# AMC.net
KiCad netlist of a schematic drawn in Altium Designer
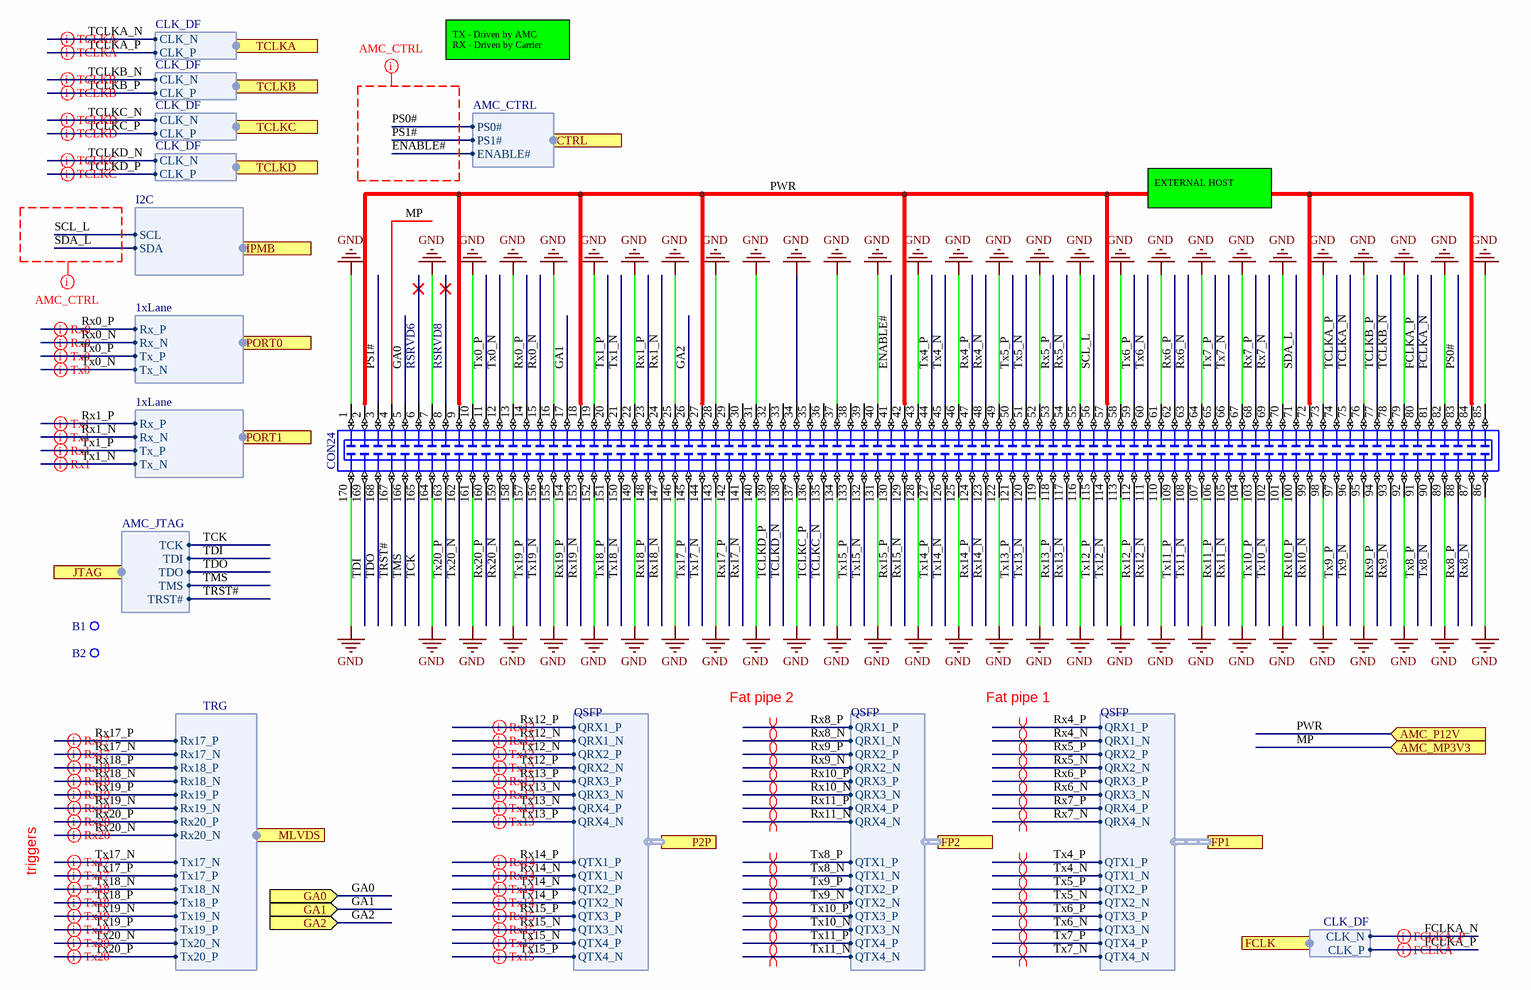
[diagram p0: AMC.SchDoc]

(export (version "E")
  (design (tool "Eeschema 10.0.6"))
  (components
    (comp (ref "B1")
      (value "Plated Hole")
      (footprint "MTG320_550")
      (description "Single Terminal Socket")
      (fields (field (name "PART NUMBER") "PLATED_HOLE3.2_PAD5.5") (field (name "AUTHOR") "CERN DEM JMW"))
      (libsource (lib "Eletro-mechanical") (part "Single Terminal Socket"))
    )
    (comp (ref "B2")
      (value "Plated Hole")
      (footprint "MTG320_550")
      (description "Single Terminal Socket")
      (fields (field (name "PART NUMBER") "PLATED_HOLE3.2_PAD5.5") (field (name "AUTHOR") "CERN DEM JMW"))
      (libsource (lib "Eletro-mechanical") (part "Single Terminal Socket"))
    )
    (comp (ref "CON24")
      (value "SAMTEC_MTCA-085-02-S-DV-SMT-K-TR")
      (footprint "SAMTEC_MTCA-085-02-S-DV-SMT-K-TR")
      (description "170 Poles,  Micro TCA (Telecom Computing Architecture) Edge Card Socket")
      (fields
        (field (name "MANUFACTURER") "SAMTEC")
        (field (name "MANUFACTURER PART NUMBER") "MTCA-085-02-S-DV-SMT-K-TR")
        (field (name "AUTHOR") "CERN DEM JLC")
      )
      (libsource (lib "Connectors") (part "Micro TCA Female 170"))
    )
  )
  (nets
    (net (code "8") (name "/ENABLE#") (class "Default")
      (node (ref "CON24") (pin "41") (pinfunction "41_41") (pintype "bidirectional"))
    )
    (net (code "9") (name "/FCLKA_N") (class "Default")
      (node (ref "CON24") (pin "81") (pinfunction "81_81") (pintype "bidirectional"))
    )
    (net (code "10") (name "/FCLKA_P") (class "Default")
      (node (ref "CON24") (pin "80") (pinfunction "80_80") (pintype "bidirectional"))
    )
    (net (code "11") (name "/GA0") (class "Default")
      (node (ref "CON24") (pin "5") (pinfunction "5_5") (pintype "bidirectional"))
    )
    (net (code "12") (name "/GA1") (class "Default")
      (node (ref "CON24") (pin "17") (pinfunction "17_17") (pintype "bidirectional"))
    )
    (net (code "13") (name "/GA2") (class "Default")
      (node (ref "CON24") (pin "26") (pinfunction "26_26") (pintype "bidirectional"))
    )
    (net (code "14") (name "/MP") (class "Default")
      (node (ref "CON24") (pin "4") (pinfunction "4_4") (pintype "bidirectional"))
    )
    (net (code "15") (name "/PS0#") (class "Default")
      (node (ref "CON24") (pin "83") (pinfunction "83_83") (pintype "bidirectional"))
    )
    (net (code "16") (name "/PS1#") (class "Default")
      (node (ref "CON24") (pin "3") (pinfunction "3_3") (pintype "bidirectional"))
    )
    (net (code "17") (name "/PWR") (class "Default")
      (node (ref "CON24") (pin "18") (pinfunction "18_18") (pintype "bidirectional"))
      (node (ref "CON24") (pin "2") (pinfunction "2_2") (pintype "bidirectional"))
      (node (ref "CON24") (pin "27") (pinfunction "27_27") (pintype "bidirectional"))
      (node (ref "CON24") (pin "42") (pinfunction "42_42") (pintype "bidirectional"))
      (node (ref "CON24") (pin "57") (pinfunction "57_57") (pintype "bidirectional"))
      (node (ref "CON24") (pin "72") (pinfunction "72_72") (pintype "bidirectional"))
      (node (ref "CON24") (pin "84") (pinfunction "84_84") (pintype "bidirectional"))
      (node (ref "CON24") (pin "9") (pinfunction "9_9") (pintype "bidirectional"))
    )
    (net (code "18") (name "/Rx0_N") (class "Default")
      (node (ref "CON24") (pin "15") (pinfunction "15_15") (pintype "bidirectional"))
    )
    (net (code "19") (name "/Rx0_P") (class "Default")
      (node (ref "CON24") (pin "14") (pinfunction "14_14") (pintype "bidirectional"))
    )
    (net (code "20") (name "/Rx1_N") (class "Default")
      (node (ref "CON24") (pin "24") (pinfunction "24_24") (pintype "bidirectional"))
    )
    (net (code "21") (name "/Rx1_P") (class "Default")
      (node (ref "CON24") (pin "23") (pinfunction "23_23") (pintype "bidirectional"))
    )
    (net (code "22") (name "/Rx4_N") (class "Default")
      (node (ref "CON24") (pin "48") (pinfunction "48_48") (pintype "bidirectional"))
    )
    (net (code "23") (name "/Rx4_P") (class "Default")
      (node (ref "CON24") (pin "47") (pinfunction "47_47") (pintype "bidirectional"))
    )
    (net (code "24") (name "/Rx5_N") (class "Default")
      (node (ref "CON24") (pin "54") (pinfunction "54_54") (pintype "bidirectional"))
    )
    (net (code "25") (name "/Rx5_P") (class "Default")
      (node (ref "CON24") (pin "53") (pinfunction "53_53") (pintype "bidirectional"))
    )
    (net (code "26") (name "/Rx6_N") (class "Default")
      (node (ref "CON24") (pin "63") (pinfunction "63_63") (pintype "bidirectional"))
    )
    (net (code "27") (name "/Rx6_P") (class "Default")
      (node (ref "CON24") (pin "62") (pinfunction "62_62") (pintype "bidirectional"))
    )
    (net (code "28") (name "/Rx7_N") (class "Default")
      (node (ref "CON24") (pin "69") (pinfunction "69_69") (pintype "bidirectional"))
    )
    (net (code "29") (name "/Rx7_P") (class "Default")
      (node (ref "CON24") (pin "68") (pinfunction "68_68") (pintype "bidirectional"))
    )
    (net (code "30") (name "/Rx8_N") (class "Default")
      (node (ref "CON24") (pin "87") (pinfunction "87_87") (pintype "bidirectional"))
    )
    (net (code "31") (name "/Rx8_P") (class "Default")
      (node (ref "CON24") (pin "88") (pinfunction "88_88") (pintype "bidirectional"))
    )
    (net (code "32") (name "/Rx9_N") (class "Default")
      (node (ref "CON24") (pin "93") (pinfunction "93_93") (pintype "bidirectional"))
    )
    (net (code "33") (name "/Rx9_P") (class "Default")
      (node (ref "CON24") (pin "94") (pinfunction "94_94") (pintype "bidirectional"))
    )
    (net (code "34") (name "/Rx10_N") (class "Default")
      (node (ref "CON24") (pin "99") (pinfunction "99_99") (pintype "bidirectional"))
    )
    (net (code "35") (name "/Rx10_P") (class "Default")
      (node (ref "CON24") (pin "100") (pinfunction "100_100") (pintype "bidirectional"))
    )
    (net (code "36") (name "/Rx11_N") (class "Default")
      (node (ref "CON24") (pin "105") (pinfunction "105_105") (pintype "bidirectional"))
    )
    (net (code "37") (name "/Rx11_P") (class "Default")
      (node (ref "CON24") (pin "106") (pinfunction "106_106") (pintype "bidirectional"))
    )
    (net (code "38") (name "/Rx12_N") (class "Default")
      (node (ref "CON24") (pin "111") (pinfunction "111_111") (pintype "bidirectional"))
    )
    (net (code "39") (name "/Rx12_P") (class "Default")
      (node (ref "CON24") (pin "112") (pinfunction "112_112") (pintype "bidirectional"))
    )
    (net (code "40") (name "/Rx13_N") (class "Default")
      (node (ref "CON24") (pin "117") (pinfunction "117_117") (pintype "bidirectional"))
    )
    (net (code "41") (name "/Rx13_P") (class "Default")
      (node (ref "CON24") (pin "118") (pinfunction "118_118") (pintype "bidirectional"))
    )
    (net (code "42") (name "/Rx14_N") (class "Default")
      (node (ref "CON24") (pin "123") (pinfunction "123_123") (pintype "bidirectional"))
    )
    (net (code "43") (name "/Rx14_P") (class "Default")
      (node (ref "CON24") (pin "124") (pinfunction "124_124") (pintype "bidirectional"))
    )
    (net (code "44") (name "/Rx15_N") (class "Default")
      (node (ref "CON24") (pin "129") (pinfunction "129_129") (pintype "bidirectional"))
    )
    (net (code "45") (name "/Rx15_P") (class "Default")
      (node (ref "CON24") (pin "130") (pinfunction "130_130") (pintype "bidirectional"))
    )
    (net (code "46") (name "/Rx17_N") (class "Default")
      (node (ref "CON24") (pin "141") (pinfunction "141_141") (pintype "bidirectional"))
    )
    (net (code "47") (name "/Rx17_P") (class "Default")
      (node (ref "CON24") (pin "142") (pinfunction "142_142") (pintype "bidirectional"))
    )
    (net (code "48") (name "/Rx18_N") (class "Default")
      (node (ref "CON24") (pin "147") (pinfunction "147_147") (pintype "bidirectional"))
    )
    (net (code "49") (name "/Rx18_P") (class "Default")
      (node (ref "CON24") (pin "148") (pinfunction "148_148") (pintype "bidirectional"))
    )
    (net (code "50") (name "/Rx19_N") (class "Default")
      (node (ref "CON24") (pin "153") (pinfunction "153_153") (pintype "bidirectional"))
    )
    (net (code "51") (name "/Rx19_P") (class "Default")
      (node (ref "CON24") (pin "154") (pinfunction "154_154") (pintype "bidirectional"))
    )
    (net (code "52") (name "/Rx20_N") (class "Default")
      (node (ref "CON24") (pin "159") (pinfunction "159_159") (pintype "bidirectional"))
    )
    (net (code "53") (name "/Rx20_P") (class "Default")
      (node (ref "CON24") (pin "160") (pinfunction "160_160") (pintype "bidirectional"))
    )
    (net (code "54") (name "/SCL_L") (class "Default")
      (node (ref "CON24") (pin "56") (pinfunction "56_56") (pintype "bidirectional"))
    )
    (net (code "55") (name "/SDA_L") (class "Default")
      (node (ref "CON24") (pin "71") (pinfunction "71_71") (pintype "bidirectional"))
    )
    (net (code "56") (name "/TCK") (class "Default")
      (node (ref "CON24") (pin "165") (pinfunction "165_165") (pintype "bidirectional"))
    )
    (net (code "57") (name "/TCLKA_N") (class "Default")
      (node (ref "CON24") (pin "75") (pinfunction "75_75") (pintype "bidirectional"))
    )
    (net (code "58") (name "/TCLKA_P") (class "Default")
      (node (ref "CON24") (pin "74") (pinfunction "74_74") (pintype "bidirectional"))
    )
    (net (code "59") (name "/TCLKB_N") (class "Default")
      (node (ref "CON24") (pin "78") (pinfunction "78_78") (pintype "bidirectional"))
    )
    (net (code "60") (name "/TCLKB_P") (class "Default")
      (node (ref "CON24") (pin "77") (pinfunction "77_77") (pintype "bidirectional"))
    )
    (net (code "61") (name "/TCLKC_N") (class "Default")
      (node (ref "CON24") (pin "135") (pinfunction "135_135") (pintype "bidirectional"))
    )
    (net (code "62") (name "/TCLKC_P") (class "Default")
      (node (ref "CON24") (pin "136") (pinfunction "136_136") (pintype "bidirectional"))
    )
    (net (code "63") (name "/TCLKD_N") (class "Default")
      (node (ref "CON24") (pin "138") (pinfunction "138_138") (pintype "bidirectional"))
    )
    (net (code "64") (name "/TCLKD_P") (class "Default")
      (node (ref "CON24") (pin "139") (pinfunction "139_139") (pintype "bidirectional"))
    )
    (net (code "65") (name "/TDI") (class "Default")
      (node (ref "CON24") (pin "169") (pinfunction "169_169") (pintype "bidirectional"))
    )
    (net (code "66") (name "/TDO") (class "Default")
      (node (ref "CON24") (pin "168") (pinfunction "168_168") (pintype "bidirectional"))
    )
    (net (code "67") (name "/TMS") (class "Default")
      (node (ref "CON24") (pin "166") (pinfunction "166_166") (pintype "bidirectional"))
    )
    (net (code "68") (name "/TRST#") (class "Default")
      (node (ref "CON24") (pin "167") (pinfunction "167_167") (pintype "bidirectional"))
    )
    (net (code "69") (name "/Tx0_N") (class "Default")
      (node (ref "CON24") (pin "12") (pinfunction "12_12") (pintype "bidirectional"))
    )
    (net (code "70") (name "/Tx0_P") (class "Default")
      (node (ref "CON24") (pin "11") (pinfunction "11_11") (pintype "bidirectional"))
    )
    (net (code "71") (name "/Tx1_N") (class "Default")
      (node (ref "CON24") (pin "21") (pinfunction "21_21") (pintype "bidirectional"))
    )
    (net (code "72") (name "/Tx1_P") (class "Default")
      (node (ref "CON24") (pin "20") (pinfunction "20_20") (pintype "bidirectional"))
    )
    (net (code "73") (name "/Tx4_N") (class "Default")
      (node (ref "CON24") (pin "45") (pinfunction "45_45") (pintype "bidirectional"))
    )
    (net (code "74") (name "/Tx4_P") (class "Default")
      (node (ref "CON24") (pin "44") (pinfunction "44_44") (pintype "bidirectional"))
    )
    (net (code "75") (name "/Tx5_N") (class "Default")
      (node (ref "CON24") (pin "51") (pinfunction "51_51") (pintype "bidirectional"))
    )
    (net (code "76") (name "/Tx5_P") (class "Default")
      (node (ref "CON24") (pin "50") (pinfunction "50_50") (pintype "bidirectional"))
    )
    (net (code "77") (name "/Tx6_N") (class "Default")
      (node (ref "CON24") (pin "60") (pinfunction "60_60") (pintype "bidirectional"))
    )
    (net (code "78") (name "/Tx6_P") (class "Default")
      (node (ref "CON24") (pin "59") (pinfunction "59_59") (pintype "bidirectional"))
    )
    (net (code "79") (name "/Tx7_N") (class "Default")
      (node (ref "CON24") (pin "66") (pinfunction "66_66") (pintype "bidirectional"))
    )
    (net (code "80") (name "/Tx7_P") (class "Default")
      (node (ref "CON24") (pin "65") (pinfunction "65_65") (pintype "bidirectional"))
    )
    (net (code "81") (name "/Tx8_N") (class "Default")
      (node (ref "CON24") (pin "90") (pinfunction "90_90") (pintype "bidirectional"))
    )
    (net (code "82") (name "/Tx8_P") (class "Default")
      (node (ref "CON24") (pin "91") (pinfunction "91_91") (pintype "bidirectional"))
    )
    (net (code "83") (name "/Tx9_N") (class "Default")
      (node (ref "CON24") (pin "96") (pinfunction "96_96") (pintype "bidirectional"))
    )
    (net (code "84") (name "/Tx9_P") (class "Default")
      (node (ref "CON24") (pin "97") (pinfunction "97_97") (pintype "bidirectional"))
    )
    (net (code "85") (name "/Tx10_N") (class "Default")
      (node (ref "CON24") (pin "102") (pinfunction "102_102") (pintype "bidirectional"))
    )
    (net (code "86") (name "/Tx10_P") (class "Default")
      (node (ref "CON24") (pin "103") (pinfunction "103_103") (pintype "bidirectional"))
    )
    (net (code "87") (name "/Tx11_N") (class "Default")
      (node (ref "CON24") (pin "108") (pinfunction "108_108") (pintype "bidirectional"))
    )
    (net (code "88") (name "/Tx11_P") (class "Default")
      (node (ref "CON24") (pin "109") (pinfunction "109_109") (pintype "bidirectional"))
    )
    (net (code "89") (name "/Tx12_N") (class "Default")
      (node (ref "CON24") (pin "114") (pinfunction "114_114") (pintype "bidirectional"))
    )
    (net (code "90") (name "/Tx12_P") (class "Default")
      (node (ref "CON24") (pin "115") (pinfunction "115_115") (pintype "bidirectional"))
    )
    (net (code "91") (name "/Tx13_N") (class "Default")
      (node (ref "CON24") (pin "120") (pinfunction "120_120") (pintype "bidirectional"))
    )
    (net (code "92") (name "/Tx13_P") (class "Default")
      (node (ref "CON24") (pin "121") (pinfunction "121_121") (pintype "bidirectional"))
    )
    (net (code "93") (name "/Tx14_N") (class "Default")
      (node (ref "CON24") (pin "126") (pinfunction "126_126") (pintype "bidirectional"))
    )
    (net (code "94") (name "/Tx14_P") (class "Default")
      (node (ref "CON24") (pin "127") (pinfunction "127_127") (pintype "bidirectional"))
    )
    (net (code "95") (name "/Tx15_N") (class "Default")
      (node (ref "CON24") (pin "132") (pinfunction "132_132") (pintype "bidirectional"))
    )
    (net (code "96") (name "/Tx15_P") (class "Default")
      (node (ref "CON24") (pin "133") (pinfunction "133_133") (pintype "bidirectional"))
    )
    (net (code "97") (name "/Tx17_N") (class "Default")
      (node (ref "CON24") (pin "144") (pinfunction "144_144") (pintype "bidirectional"))
    )
    (net (code "98") (name "/Tx17_P") (class "Default")
      (node (ref "CON24") (pin "145") (pinfunction "145_145") (pintype "bidirectional"))
    )
    (net (code "99") (name "/Tx18_N") (class "Default")
      (node (ref "CON24") (pin "150") (pinfunction "150_150") (pintype "bidirectional"))
    )
    (net (code "100") (name "/Tx18_P") (class "Default")
      (node (ref "CON24") (pin "151") (pinfunction "151_151") (pintype "bidirectional"))
    )
    (net (code "101") (name "/Tx19_N") (class "Default")
      (node (ref "CON24") (pin "156") (pinfunction "156_156") (pintype "bidirectional"))
    )
    (net (code "102") (name "/Tx19_P") (class "Default")
      (node (ref "CON24") (pin "157") (pinfunction "157_157") (pintype "bidirectional"))
    )
    (net (code "103") (name "/Tx20_N") (class "Default")
      (node (ref "CON24") (pin "162") (pinfunction "162_162") (pintype "bidirectional"))
    )
    (net (code "104") (name "/Tx20_P") (class "Default")
      (node (ref "CON24") (pin "163") (pinfunction "163_163") (pintype "bidirectional"))
    )
    (net (code "112") (name "GND") (class "Default")
      (node (ref "CON24") (pin "1") (pinfunction "1_1") (pintype "bidirectional"))
      (node (ref "CON24") (pin "10") (pinfunction "10_10") (pintype "bidirectional"))
      (node (ref "CON24") (pin "101") (pinfunction "101_101") (pintype "bidirectional"))
      (node (ref "CON24") (pin "104") (pinfunction "104_104") (pintype "bidirectional"))
      (node (ref "CON24") (pin "107") (pinfunction "107_107") (pintype "bidirectional"))
      (node (ref "CON24") (pin "110") (pinfunction "110_110") (pintype "bidirectional"))
      (node (ref "CON24") (pin "113") (pinfunction "113_113") (pintype "bidirectional"))
      (node (ref "CON24") (pin "116") (pinfunction "116_116") (pintype "bidirectional"))
      (node (ref "CON24") (pin "119") (pinfunction "119_119") (pintype "bidirectional"))
      (node (ref "CON24") (pin "122") (pinfunction "122_122") (pintype "bidirectional"))
      (node (ref "CON24") (pin "125") (pinfunction "125_125") (pintype "bidirectional"))
      (node (ref "CON24") (pin "128") (pinfunction "128_128") (pintype "bidirectional"))
      (node (ref "CON24") (pin "13") (pinfunction "13_13") (pintype "bidirectional"))
      (node (ref "CON24") (pin "131") (pinfunction "131_131") (pintype "bidirectional"))
      (node (ref "CON24") (pin "134") (pinfunction "134_134") (pintype "bidirectional"))
      (node (ref "CON24") (pin "137") (pinfunction "137_137") (pintype "bidirectional"))
      (node (ref "CON24") (pin "140") (pinfunction "140_140") (pintype "bidirectional"))
      (node (ref "CON24") (pin "143") (pinfunction "143_143") (pintype "bidirectional"))
      (node (ref "CON24") (pin "146") (pinfunction "146_146") (pintype "bidirectional"))
      (node (ref "CON24") (pin "149") (pinfunction "149_149") (pintype "bidirectional"))
      (node (ref "CON24") (pin "152") (pinfunction "152_152") (pintype "bidirectional"))
      (node (ref "CON24") (pin "155") (pinfunction "155_155") (pintype "bidirectional"))
      (node (ref "CON24") (pin "158") (pinfunction "158_158") (pintype "bidirectional"))
      (node (ref "CON24") (pin "16") (pinfunction "16_16") (pintype "bidirectional"))
      (node (ref "CON24") (pin "161") (pinfunction "161_161") (pintype "bidirectional"))
      (node (ref "CON24") (pin "164") (pinfunction "164_164") (pintype "bidirectional"))
      (node (ref "CON24") (pin "170") (pinfunction "170_170") (pintype "bidirectional"))
      (node (ref "CON24") (pin "19") (pinfunction "19_19") (pintype "bidirectional"))
      (node (ref "CON24") (pin "22") (pinfunction "22_22") (pintype "bidirectional"))
      (node (ref "CON24") (pin "25") (pinfunction "25_25") (pintype "bidirectional"))
      (node (ref "CON24") (pin "28") (pinfunction "28_28") (pintype "bidirectional"))
      (node (ref "CON24") (pin "31") (pinfunction "31_31") (pintype "bidirectional"))
      (node (ref "CON24") (pin "34") (pinfunction "34_34") (pintype "bidirectional"))
      (node (ref "CON24") (pin "37") (pinfunction "37_37") (pintype "bidirectional"))
      (node (ref "CON24") (pin "40") (pinfunction "40_40") (pintype "bidirectional"))
      (node (ref "CON24") (pin "43") (pinfunction "43_43") (pintype "bidirectional"))
      (node (ref "CON24") (pin "46") (pinfunction "46_46") (pintype "bidirectional"))
      (node (ref "CON24") (pin "49") (pinfunction "49_49") (pintype "bidirectional"))
      (node (ref "CON24") (pin "52") (pinfunction "52_52") (pintype "bidirectional"))
      (node (ref "CON24") (pin "55") (pinfunction "55_55") (pintype "bidirectional"))
      (node (ref "CON24") (pin "58") (pinfunction "58_58") (pintype "bidirectional"))
      (node (ref "CON24") (pin "61") (pinfunction "61_61") (pintype "bidirectional"))
      (node (ref "CON24") (pin "64") (pinfunction "64_64") (pintype "bidirectional"))
      (node (ref "CON24") (pin "67") (pinfunction "67_67") (pintype "bidirectional"))
      (node (ref "CON24") (pin "7") (pinfunction "7_7") (pintype "bidirectional"))
      (node (ref "CON24") (pin "70") (pinfunction "70_70") (pintype "bidirectional"))
      (node (ref "CON24") (pin "73") (pinfunction "73_73") (pintype "bidirectional"))
      (node (ref "CON24") (pin "76") (pinfunction "76_76") (pintype "bidirectional"))
      (node (ref "CON24") (pin "79") (pinfunction "79_79") (pintype "bidirectional"))
      (node (ref "CON24") (pin "82") (pinfunction "82_82") (pintype "bidirectional"))
      (node (ref "CON24") (pin "85") (pinfunction "85_85") (pintype "bidirectional"))
      (node (ref "CON24") (pin "86") (pinfunction "86_86") (pintype "bidirectional"))
      (node (ref "CON24") (pin "89") (pinfunction "89_89") (pintype "bidirectional"))
      (node (ref "CON24") (pin "92") (pinfunction "92_92") (pintype "bidirectional"))
      (node (ref "CON24") (pin "95") (pinfunction "95_95") (pintype "bidirectional"))
      (node (ref "CON24") (pin "98") (pinfunction "98_98") (pintype "bidirectional"))
    )
    (net (code "113") (name "unconnected-(B1-Pad1)") (class "Default")
      (node (ref "B1") (pin "1") (pinfunction "1_1") (pintype "bidirectional"))
    )
    (net (code "114") (name "unconnected-(B2-Pad1)") (class "Default")
      (node (ref "B2") (pin "1") (pinfunction "1_1") (pintype "bidirectional"))
    )
    (net (code "115") (name "unconnected-(CON24-Pad6)") (class "Default")
      (node (ref "CON24") (pin "6") (pinfunction "6_6") (pintype "bidirectional"))
    )
    (net (code "116") (name "unconnected-(CON24-Pad8)") (class "Default")
      (node (ref "CON24") (pin "8") (pinfunction "8_8") (pintype "bidirectional"))
    )
    (net (code "117") (name "unconnected-(CON24-Pad29)") (class "Default")
      (node (ref "CON24") (pin "29") (pinfunction "29_29") (pintype "bidirectional"))
    )
    (net (code "118") (name "unconnected-(CON24-Pad30)") (class "Default")
      (node (ref "CON24") (pin "30") (pinfunction "30_30") (pintype "bidirectional"))
    )
    (net (code "119") (name "unconnected-(CON24-Pad32)") (class "Default")
      (node (ref "CON24") (pin "32") (pinfunction "32_32") (pintype "bidirectional"))
    )
    (net (code "120") (name "unconnected-(CON24-Pad33)") (class "Default")
      (node (ref "CON24") (pin "33") (pinfunction "33_33") (pintype "bidirectional"))
    )
    (net (code "121") (name "unconnected-(CON24-Pad35)") (class "Default")
      (node (ref "CON24") (pin "35") (pinfunction "35_35") (pintype "bidirectional"))
    )
    (net (code "122") (name "unconnected-(CON24-Pad36)") (class "Default")
      (node (ref "CON24") (pin "36") (pinfunction "36_36") (pintype "bidirectional"))
    )
    (net (code "123") (name "unconnected-(CON24-Pad38)") (class "Default")
      (node (ref "CON24") (pin "38") (pinfunction "38_38") (pintype "bidirectional"))
    )
    (net (code "124") (name "unconnected-(CON24-Pad39)") (class "Default")
      (node (ref "CON24") (pin "39") (pinfunction "39_39") (pintype "bidirectional"))
    )
  )
)
